# SD_Holder.net
KiCad netlist of a schematic drawn in Altium Designer
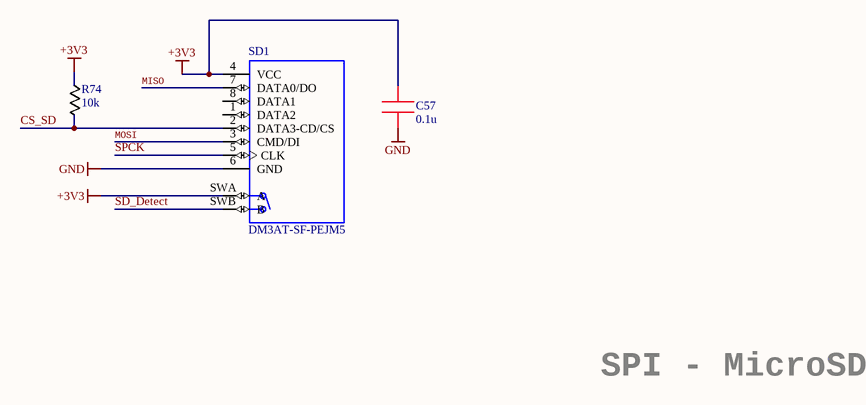
[diagram p0: SD Holder.SchDoc]

(export (version "E")
  (design (tool "Eeschema 10.0.6"))
  (components
    (comp (ref "C57")
      (value "0.1u")
      (footprint "0603 CAP")
      (description "GRM188R71E104KA01D")
      (libsource (lib "kontr") (part "0603 CAP"))
    )
    (comp (ref "R74")
      (value "10k")
      (footprint "0603 - RES")
      (description "RC0603JR-0710K")
      (libsource (lib "kontr") (part "0603 RES"))
    )
    (comp (ref "SD1")
      (value "DM3AT-SF-PEJM5")
      (footprint "DM3AT-SF-PEJM5")
      (libsource (lib "kontr") (part "DM3AT-SF-PEJM5"))
    )
  )
  (nets
    (net (code "1") (name "+3V3") (class "Default")
      (node (ref "C57") (pin "2") (pinfunction "2_2") (pintype "passive"))
      (node (ref "R74") (pin "1") (pintype "passive"))
      (node (ref "SD1") (pin "4") (pinfunction "VCC_4") (pintype "power_in"))
      (node (ref "SD1") (pin "SWA") (pinfunction "A_SWA") (pintype "bidirectional"))
    )
    (net (code "2") (name "/CS_SD") (class "Default")
      (node (ref "R74") (pin "2") (pintype "passive"))
      (node (ref "SD1") (pin "2") (pinfunction "DATA3-CD/CS_2") (pintype "bidirectional"))
    )
    (net (code "3") (name "/MISO") (class "Default")
      (node (ref "SD1") (pin "7") (pinfunction "DATA0/DO_7") (pintype "bidirectional"))
    )
    (net (code "4") (name "/MOSI") (class "Default")
      (node (ref "SD1") (pin "3") (pinfunction "CMD/DI_3") (pintype "bidirectional"))
    )
    (net (code "5") (name "/SD_Detect") (class "Default")
      (node (ref "SD1") (pin "SWB") (pinfunction "B_SWB") (pintype "bidirectional"))
    )
    (net (code "6") (name "/SPCK") (class "Default")
      (node (ref "SD1") (pin "5") (pinfunction "CLK_5") (pintype "bidirectional"))
    )
    (net (code "7") (name "GND") (class "Default")
      (node (ref "C57") (pin "1") (pinfunction "1_1") (pintype "passive"))
      (node (ref "SD1") (pin "6") (pinfunction "GND_6") (pintype "power_in"))
    )
    (net (code "8") (name "unconnected-(SD1-DATA1-Pad8)") (class "Default")
      (node (ref "SD1") (pin "8") (pinfunction "DATA1_8") (pintype "bidirectional"))
    )
    (net (code "9") (name "unconnected-(SD1-DATA2-Pad1)") (class "Default")
      (node (ref "SD1") (pin "1") (pinfunction "DATA2_1") (pintype "bidirectional"))
    )
  )
)
